# main.net
KiCad netlist of a schematic drawn in Altium Designer
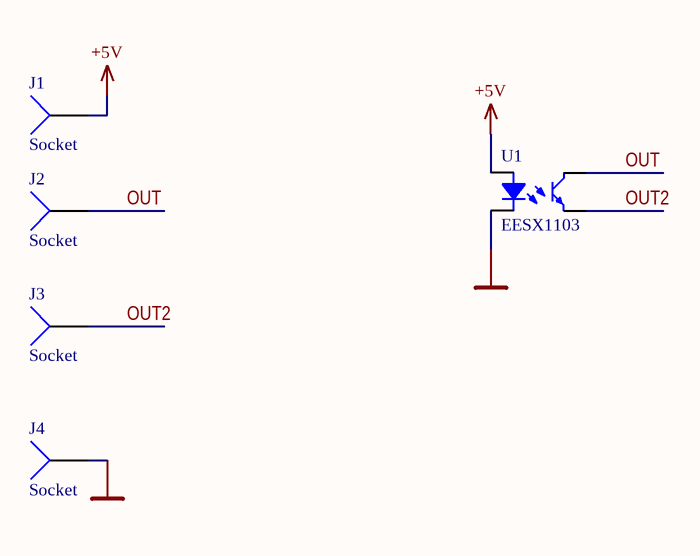
[diagram p0: main.SchDoc]

(export (version "E")
  (design (tool "Eeschema 10.0.6"))
  (components
    (comp (ref "J1")
      (value "Socket")
      (footprint "PIN1")
      (fields (field (name "PUBLISHER") "Altium Limited"))
      (libsource (lib "Miscellaneous Connectors") (part "Socket"))
    )
    (comp (ref "J2")
      (value "Socket")
      (footprint "PIN1")
      (fields (field (name "PUBLISHER") "Altium Limited"))
      (libsource (lib "Miscellaneous Connectors") (part "Socket"))
    )
    (comp (ref "J3")
      (value "Socket")
      (footprint "PIN1")
      (fields (field (name "PUBLISHER") "Altium Limited"))
      (libsource (lib "Miscellaneous Connectors") (part "Socket"))
    )
    (comp (ref "J4")
      (value "Socket")
      (footprint "PIN1")
      (fields (field (name "PUBLISHER") "Altium Limited"))
      (libsource (lib "Miscellaneous Connectors") (part "Socket"))
    )
    (comp (ref "U1") (value "EESX1103") (footprint "EESX1103") (libsource (lib "EESX1103") (part "EESX1103")))
  )
  (nets
    (net (code "1") (name "+5V") (class "Default")
      (node (ref "J1") (pin "1") (pinfunction "1_1") (pintype "passive"))
      (node (ref "U1") (pin "1") (pinfunction "1_1") (pintype "passive"))
    )
    (net (code "2") (name "/OUT") (class "Default")
      (node (ref "J2") (pin "1") (pinfunction "1_1") (pintype "passive"))
      (node (ref "U1") (pin "4") (pinfunction "4_4") (pintype "passive"))
    )
    (net (code "3") (name "/OUT2") (class "Default")
      (node (ref "J3") (pin "1") (pinfunction "1_1") (pintype "passive"))
      (node (ref "U1") (pin "3") (pinfunction "3_3") (pintype "passive"))
    )
    (net (code "4") (name "GND") (class "Default")
      (node (ref "J4") (pin "1") (pinfunction "1_1") (pintype "passive"))
      (node (ref "U1") (pin "2") (pinfunction "2_2") (pintype "passive"))
    )
  )
)
